# NRF24l01.net
KiCad netlist of a schematic drawn in Altium Designer
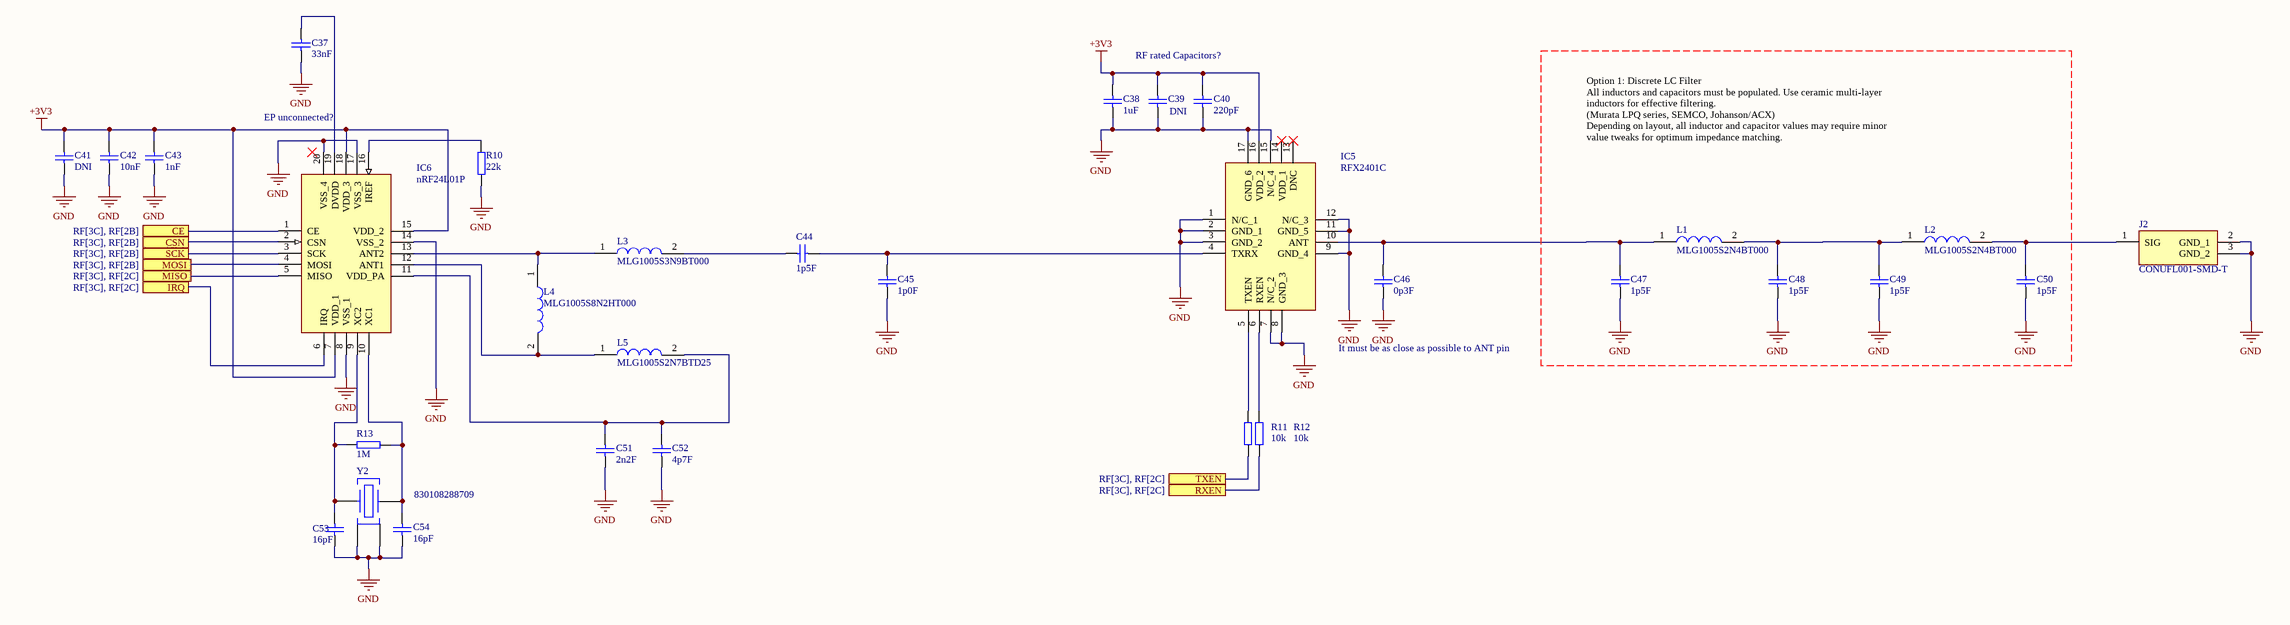
[diagram p0: NRF24l01.SchDoc]

(export (version "E")
  (design (tool "Eeschema 10.0.6"))
  (components
    (comp (ref "C37")
      (value "33nF")
      (footprint "CAP0402")
      (fields
        (field (name "VOLTAGE") "6V3")
        (field (name "MANUFACTURER_PART_NUMBER") "GRM155R61H333KE14D")
        (field (name "Comment") "Cap0402")
      )
      (libsource (lib "capacitorsSMD") (part "Cap0402"))
    )
    (comp (ref "C38")
      (value "1uF")
      (footprint "CAP0402")
      (fields
        (field (name "VOLTAGE") "6V3")
        (field (name "MANUFACTURER_PART_NUMBER") "GRM155R61H105KE05J")
        (field (name "Comment") "Cap0402")
      )
      (libsource (lib "capacitorsSMD") (part "Cap0402"))
    )
    (comp (ref "C39")
      (value "DNI")
      (footprint "CAP0402")
      (fields (field (name "VOLTAGE") "6V3") (field (name "Comment") "Cap0402"))
      (libsource (lib "capacitorsSMD") (part "Cap0402"))
    )
    (comp (ref "C40")
      (value "220pF")
      (footprint "CAP0402")
      (fields
        (field (name "VOLTAGE") "6V3")
        (field (name "MANUFACTURER_PART_NUMBER") "GRM1555C1H221JA01D")
        (field (name "Comment") "Cap0402")
      )
      (libsource (lib "capacitorsSMD") (part "Cap0402"))
    )
    (comp (ref "C41")
      (value "DNI")
      (footprint "CAP0402")
      (fields (field (name "VOLTAGE") "6V3") (field (name "Comment") "Cap0402"))
      (libsource (lib "capacitorsSMD") (part "Cap0402"))
    )
    (comp (ref "C42")
      (value "10nF")
      (footprint "CAP0402")
      (fields
        (field (name "VOLTAGE") "6V3")
        (field (name "MANUFACTURER_PART_NUMBER") "GRM155R71H103MA88D")
        (field (name "Comment") "Cap0402")
      )
      (libsource (lib "capacitorsSMD") (part "Cap0402"))
    )
    (comp (ref "C43")
      (value "1nF")
      (footprint "CAP0402")
      (fields
        (field (name "VOLTAGE") "6V3")
        (field (name "MANUFACTURER_PART_NUMBER") "GRM155R71H102KA01J")
        (field (name "Comment") "Cap0402")
      )
      (libsource (lib "capacitorsSMD") (part "Cap0402"))
    )
    (comp (ref "C44")
      (value "1p5F")
      (footprint "CAP0402")
      (description "RF NP0")
      (fields (field (name "VOLTAGE") "6V3") (field (name "MANUFACTURER_PART_NUMBER") "GRM1555C1H1R5BA01J"))
      (libsource (lib "capacitorsSMD") (part "Cap0402"))
    )
    (comp (ref "C45")
      (value "1p0F")
      (footprint "CAP0402")
      (description "RF NP0")
      (fields (field (name "VOLTAGE") "6V3") (field (name "MANUFACTURER_PART_NUMBER") "GCM1555C1H1R0BA16D"))
      (libsource (lib "capacitorsSMD") (part "Cap0402"))
    )
    (comp (ref "C46")
      (value "0p3F")
      (footprint "CAP0402")
      (description "RF NP0")
      (fields (field (name "VOLTAGE") "6V3") (field (name "MANUFACTURER_PART_NUMBER") "GJM1555C1HR30BB01J"))
      (libsource (lib "capacitorsSMD") (part "Cap0402"))
    )
    (comp (ref "C47")
      (value "1p5F")
      (footprint "CAP0402")
      (description "RF NP0")
      (fields (field (name "VOLTAGE") "6V3") (field (name "MANUFACTURER_PART_NUMBER") "GRM1555C1H1R5BA01J"))
      (libsource (lib "capacitorsSMD") (part "Cap0402"))
    )
    (comp (ref "C48")
      (value "1p5F")
      (footprint "CAP0402")
      (description "RF NP0")
      (fields (field (name "VOLTAGE") "6V3") (field (name "MANUFACTURER_PART_NUMBER") "GRM1555C1H1R5BA01J"))
      (libsource (lib "capacitorsSMD") (part "Cap0402"))
    )
    (comp (ref "C49")
      (value "1p5F")
      (footprint "CAP0402")
      (description "RF NP0")
      (fields (field (name "VOLTAGE") "6V3") (field (name "MANUFACTURER_PART_NUMBER") "GRM1555C1H1R5BA01J"))
      (libsource (lib "capacitorsSMD") (part "Cap0402"))
    )
    (comp (ref "C50")
      (value "1p5F")
      (footprint "CAP0402")
      (description "RF NP0")
      (fields (field (name "VOLTAGE") "6V3") (field (name "MANUFACTURER_PART_NUMBER") "GRM1555C1H1R5BA01J"))
      (libsource (lib "capacitorsSMD") (part "Cap0402"))
    )
    (comp (ref "C51")
      (value "2n2F")
      (footprint "CAP0402")
      (description "RF NP0")
      (fields (field (name "VOLTAGE") "6V3") (field (name "MANUFACTURER_PART_NUMBER") "GRM1555C1H222GA01D"))
      (libsource (lib "capacitorsSMD") (part "Cap0402"))
    )
    (comp (ref "C52")
      (value "4p7F")
      (footprint "CAP0402")
      (description "RF NP0")
      (fields (field (name "VOLTAGE") "6V3") (field (name "MANUFACTURER_PART_NUMBER") "GJM1555C1H4R7CB01D"))
      (libsource (lib "capacitorsSMD") (part "Cap0402"))
    )
    (comp (ref "C53")
      (value "16pF")
      (footprint "CAP0402")
      (description "NP0")
      (fields (field (name "VOLTAGE") "6V3") (field (name "MANUFACTURER_PART_NUMBER") "GRT1555C1H160FA02D"))
      (libsource (lib "capacitorsSMD") (part "Cap0402"))
    )
    (comp (ref "C54")
      (value "16pF")
      (footprint "CAP0402")
      (description "NP0")
      (fields (field (name "VOLTAGE") "6V3") (field (name "MANUFACTURER_PART_NUMBER") "GRT1555C1H160FA02D"))
      (libsource (lib "capacitorsSMD") (part "Cap0402"))
    )
    (comp (ref "IC5")
      (value "RFX2401C")
      (footprint "SamacSys:QFN50P300X300X60-17N-D")
      (description "Integrated Circuit")
      (libsource (lib "*") (part "RFX2401C"))
    )
    (comp (ref "IC6")
      (value "nRF24L01P")
      (footprint "SamacSys:QFN50P400X400X95-21N-D")
      (description "Integrated Circuit")
      (libsource (lib "SamacSys") (part "nRF24L01P"))
    )
    (comp (ref "J2")
      (value "CONUFL001-SMD-T")
      (footprint "SamacSys:CONUFL001-SMD")
      (description "Connector")
      (fields (field (name "MOUSER PART NUMBER") "712-CONUFL001-SMD-T"))
      (libsource (lib "*") (part "CONUFL001-SMD-T"))
    )
    (comp (ref "L1")
      (value "MLG1005S2N4BT000")
      (footprint "SamacSys:MLG1005")
      (description "Inductor")
      (libsource (lib "*") (part "MLG1005S2N4BT000"))
    )
    (comp (ref "L2")
      (value "MLG1005S2N4BT000")
      (footprint "SamacSys:MLG1005")
      (description "Inductor")
      (libsource (lib "*") (part "MLG1005S2N4BT000"))
    )
    (comp (ref "L3")
      (value "MLG1005S3N9BT000")
      (footprint "SamacSys:MLG1005")
      (description "Inductor")
      (libsource (lib "*") (part "MLG1005S3N9BT000"))
    )
    (comp (ref "L4")
      (value "MLG1005S8N2HT000")
      (footprint "SamacSys:MLG1005")
      (description "Inductor")
      (libsource (lib "*") (part "MLG1005S8N2HT000"))
    )
    (comp (ref "L5")
      (value "MLG1005S2N7BTD25")
      (footprint "SamacSys:MLG1005")
      (description "Inductor")
      (libsource (lib "*") (part "MLG1005S2N7BTD25"))
    )
    (comp (ref "R10")
      (value "22k")
      (footprint "RES0402")
      (fields (field (name "MANUFACTURER_PART_NUMBER") "RC0402JR-13100KL") (field (name "Comment") "Res0402"))
      (libsource (lib "resistorSMD") (part "Res0402"))
    )
    (comp (ref "R11")
      (value "10k")
      (footprint "RES0402")
      (fields (field (name "MANUFACTURER_PART_NUMBER") "ERA-2AED103X") (field (name "Comment") "Res0402"))
      (libsource (lib "resistorSMD") (part "Res0402"))
    )
    (comp (ref "R12")
      (value "10k")
      (footprint "RES0402")
      (fields (field (name "MANUFACTURER_PART_NUMBER") "ERA-2AED103X") (field (name "Comment") "Res0402"))
      (libsource (lib "resistorSMD") (part "Res0402"))
    )
    (comp (ref "R13")
      (value "1M")
      (footprint "RES0402")
      (fields (field (name "MANUFACTURER_PART_NUMBER") "RK73H1ETTP1004F") (field (name "Comment") "Res0402"))
      (libsource (lib "resistorSMD") (part "Res0402"))
    )
    (comp (ref "Y2")
      (value "830108288709")
      (footprint "SamacSys:830108288709")
      (description "Crystal or Oscillator")
      (libsource (lib "SamacSys") (part "830108288709"))
    )
  )
  (nets
    (net (code "1") (name "+3V3") (class "Default")
      (node (ref "C38") (pin "2") (pinfunction "2_2") (pintype "passive"))
      (node (ref "C39") (pin "2") (pinfunction "2_2") (pintype "passive"))
      (node (ref "C40") (pin "2") (pinfunction "2_2") (pintype "passive"))
      (node (ref "C41") (pin "2") (pinfunction "2_2") (pintype "passive"))
      (node (ref "C42") (pin "2") (pinfunction "2_2") (pintype "passive"))
      (node (ref "C43") (pin "2") (pinfunction "2_2") (pintype "passive"))
      (node (ref "IC5") (pin "16") (pinfunction "VDD_2_16") (pintype "passive"))
      (node (ref "IC6") (pin "15") (pinfunction "VDD_2_15") (pintype "power_in"))
      (node (ref "IC6") (pin "18") (pinfunction "VDD_3_18") (pintype "power_in"))
      (node (ref "IC6") (pin "7") (pinfunction "VDD_1_7") (pintype "power_in"))
    )
    (net (code "2") (name "/CE") (class "Default")
      (node (ref "IC6") (pin "1") (pinfunction "CE_1") (pintype "passive"))
    )
    (net (code "3") (name "/CSN") (class "Default")
      (node (ref "IC6") (pin "2") (pinfunction "CSN_2") (pintype "input"))
    )
    (net (code "4") (name "/IRQ") (class "Default")
      (node (ref "IC6") (pin "6") (pinfunction "IRQ_6") (pintype "passive"))
    )
    (net (code "5") (name "/MISO") (class "Default")
      (node (ref "IC6") (pin "5") (pinfunction "MISO_5") (pintype "passive"))
    )
    (net (code "6") (name "/MOSI") (class "Default")
      (node (ref "IC6") (pin "4") (pinfunction "MOSI_4") (pintype "passive"))
    )
    (net (code "7") (name "/RXEN") (class "Default")
      (node (ref "R12") (pin "1") (pinfunction "1_1") (pintype "passive"))
    )
    (net (code "8") (name "/SCK") (class "Default")
      (node (ref "IC6") (pin "3") (pinfunction "SCK_3") (pintype "passive"))
    )
    (net (code "9") (name "/TXEN") (class "Default")
      (node (ref "R11") (pin "1") (pinfunction "1_1") (pintype "passive"))
    )
    (net (code "10") (name "GND") (class "Default")
      (node (ref "C37") (pin "1") (pinfunction "1_1") (pintype "passive"))
      (node (ref "C38") (pin "1") (pinfunction "1_1") (pintype "passive"))
      (node (ref "C39") (pin "1") (pinfunction "1_1") (pintype "passive"))
      (node (ref "C40") (pin "1") (pinfunction "1_1") (pintype "passive"))
      (node (ref "C41") (pin "1") (pinfunction "1_1") (pintype "passive"))
      (node (ref "C42") (pin "1") (pinfunction "1_1") (pintype "passive"))
      (node (ref "C43") (pin "1") (pinfunction "1_1") (pintype "passive"))
      (node (ref "C45") (pin "1") (pinfunction "1_1") (pintype "passive"))
      (node (ref "C46") (pin "1") (pinfunction "1_1") (pintype "passive"))
      (node (ref "C47") (pin "1") (pinfunction "1_1") (pintype "passive"))
      (node (ref "C48") (pin "1") (pinfunction "1_1") (pintype "passive"))
      (node (ref "C49") (pin "1") (pinfunction "1_1") (pintype "passive"))
      (node (ref "C50") (pin "1") (pinfunction "1_1") (pintype "passive"))
      (node (ref "C51") (pin "1") (pinfunction "1_1") (pintype "passive"))
      (node (ref "C52") (pin "1") (pinfunction "1_1") (pintype "passive"))
      (node (ref "C53") (pin "1") (pinfunction "1_1") (pintype "passive"))
      (node (ref "C54") (pin "1") (pinfunction "1_1") (pintype "passive"))
      (node (ref "IC5") (pin "1") (pinfunction "N/C_1_1") (pintype "passive"))
      (node (ref "IC5") (pin "11") (pinfunction "GND_5_11") (pintype "passive"))
      (node (ref "IC5") (pin "12") (pinfunction "N/C_3_12") (pintype "passive"))
      (node (ref "IC5") (pin "15") (pinfunction "N/C_4_15") (pintype "passive"))
      (node (ref "IC5") (pin "17") (pinfunction "GND_6_17") (pintype "passive"))
      (node (ref "IC5") (pin "2") (pinfunction "GND_1_2") (pintype "passive"))
      (node (ref "IC5") (pin "3") (pinfunction "GND_2_3") (pintype "passive"))
      (node (ref "IC5") (pin "7") (pinfunction "N/C_2_7") (pintype "passive"))
      (node (ref "IC5") (pin "8") (pinfunction "GND_3_8") (pintype "passive"))
      (node (ref "IC5") (pin "9") (pinfunction "GND_4_9") (pintype "passive"))
      (node (ref "IC6") (pin "14") (pinfunction "VSS_2_14") (pintype "power_in"))
      (node (ref "IC6") (pin "17") (pinfunction "VSS_3_17") (pintype "power_in"))
      (node (ref "IC6") (pin "20") (pinfunction "VSS_4_20") (pintype "power_in"))
      (node (ref "IC6") (pin "8") (pinfunction "VSS_1_8") (pintype "power_in"))
      (node (ref "J2") (pin "2") (pinfunction "GND_1_2") (pintype "passive"))
      (node (ref "J2") (pin "3") (pinfunction "GND_2_3") (pintype "passive"))
      (node (ref "R10") (pin "1") (pinfunction "1_1") (pintype "passive"))
      (node (ref "Y2") (pin "2") (pinfunction "GND_1_2") (pintype "passive"))
      (node (ref "Y2") (pin "4") (pinfunction "GND_2_4") (pintype "passive"))
    )
    (net (code "11") (name "Net-(C44-Pad2)") (class "Default")
      (node (ref "C44") (pin "2") (pinfunction "2_2") (pintype "passive"))
      (node (ref "L3") (pin "2") (pinfunction "2_2") (pintype "passive"))
    )
    (net (code "12") (name "Net-(C48-Pad2)") (class "Default")
      (node (ref "C48") (pin "2") (pinfunction "2_2") (pintype "passive"))
      (node (ref "C49") (pin "2") (pinfunction "2_2") (pintype "passive"))
      (node (ref "L1") (pin "2") (pinfunction "2_2") (pintype "passive"))
      (node (ref "L2") (pin "1") (pinfunction "1_1") (pintype "passive"))
    )
    (net (code "13") (name "Net-(IC5-ANT)") (class "Default")
      (node (ref "C46") (pin "2") (pinfunction "2_2") (pintype "passive"))
      (node (ref "C47") (pin "2") (pinfunction "2_2") (pintype "passive"))
      (node (ref "IC5") (pin "10") (pinfunction "ANT_10") (pintype "passive"))
      (node (ref "L1") (pin "1") (pinfunction "1_1") (pintype "passive"))
    )
    (net (code "14") (name "Net-(IC5-RXEN)") (class "Default")
      (node (ref "IC5") (pin "6") (pinfunction "RXEN_6") (pintype "passive"))
      (node (ref "R12") (pin "2") (pinfunction "2_2") (pintype "passive"))
    )
    (net (code "15") (name "Net-(IC5-TXEN)") (class "Default")
      (node (ref "IC5") (pin "5") (pinfunction "TXEN_5") (pintype "passive"))
      (node (ref "R11") (pin "2") (pinfunction "2_2") (pintype "passive"))
    )
    (net (code "16") (name "Net-(IC5-TXRX)") (class "Default")
      (node (ref "C44") (pin "1") (pinfunction "1_1") (pintype "passive"))
      (node (ref "C45") (pin "2") (pinfunction "2_2") (pintype "passive"))
      (node (ref "IC5") (pin "4") (pinfunction "TXRX_4") (pintype "passive"))
    )
    (net (code "17") (name "Net-(IC6-ANT1)") (class "Default")
      (node (ref "IC6") (pin "12") (pinfunction "ANT1_12") (pintype "passive"))
      (node (ref "L4") (pin "2") (pinfunction "2_2") (pintype "passive"))
      (node (ref "L5") (pin "1") (pinfunction "1_1") (pintype "passive"))
    )
    (net (code "18") (name "Net-(IC6-ANT2)") (class "Default")
      (node (ref "IC6") (pin "13") (pinfunction "ANT2_13") (pintype "passive"))
      (node (ref "L3") (pin "1") (pinfunction "1_1") (pintype "passive"))
      (node (ref "L4") (pin "1") (pinfunction "1_1") (pintype "passive"))
    )
    (net (code "19") (name "Net-(IC6-DVDD)") (class "Default")
      (node (ref "C37") (pin "2") (pinfunction "2_2") (pintype "passive"))
      (node (ref "IC6") (pin "19") (pinfunction "DVDD_19") (pintype "power_in"))
    )
    (net (code "20") (name "Net-(IC6-IREF)") (class "Default")
      (node (ref "IC6") (pin "16") (pinfunction "IREF_16") (pintype "input"))
      (node (ref "R10") (pin "2") (pinfunction "2_2") (pintype "passive"))
    )
    (net (code "21") (name "Net-(IC6-VDD_PA)") (class "Default")
      (node (ref "C51") (pin "2") (pinfunction "2_2") (pintype "passive"))
      (node (ref "C52") (pin "2") (pinfunction "2_2") (pintype "passive"))
      (node (ref "IC6") (pin "11") (pinfunction "VDD_PA_11") (pintype "power_in"))
      (node (ref "L5") (pin "2") (pinfunction "2_2") (pintype "passive"))
    )
    (net (code "22") (name "Net-(IC6-XC1)") (class "Default")
      (node (ref "C54") (pin "2") (pinfunction "2_2") (pintype "passive"))
      (node (ref "IC6") (pin "10") (pinfunction "XC1_10") (pintype "passive"))
      (node (ref "R13") (pin "2") (pinfunction "2_2") (pintype "passive"))
      (node (ref "Y2") (pin "3") (pinfunction "CRYSTAL_2_3") (pintype "passive"))
    )
    (net (code "23") (name "Net-(IC6-XC2)") (class "Default")
      (node (ref "C53") (pin "2") (pinfunction "2_2") (pintype "passive"))
      (node (ref "IC6") (pin "9") (pinfunction "XC2_9") (pintype "passive"))
      (node (ref "R13") (pin "1") (pinfunction "1_1") (pintype "passive"))
      (node (ref "Y2") (pin "1") (pinfunction "CRYSTAL_1_1") (pintype "passive"))
    )
    (net (code "24") (name "Net-(J2-SIG)") (class "Default")
      (node (ref "C50") (pin "2") (pinfunction "2_2") (pintype "passive"))
      (node (ref "J2") (pin "1") (pinfunction "SIG_1") (pintype "passive"))
      (node (ref "L2") (pin "2") (pinfunction "2_2") (pintype "passive"))
    )
    (net (code "25") (name "unconnected-(IC5-DNC-Pad13)") (class "Default")
      (node (ref "IC5") (pin "13") (pinfunction "DNC_13") (pintype "passive+no_connect"))
    )
    (net (code "26") (name "unconnected-(IC5-VDD_1-Pad14)") (class "Default")
      (node (ref "IC5") (pin "14") (pinfunction "VDD_1_14") (pintype "passive+no_connect"))
    )
  )
)
